# OR_timing_pulse.net
KiCad netlist of a schematic drawn in EAGLE
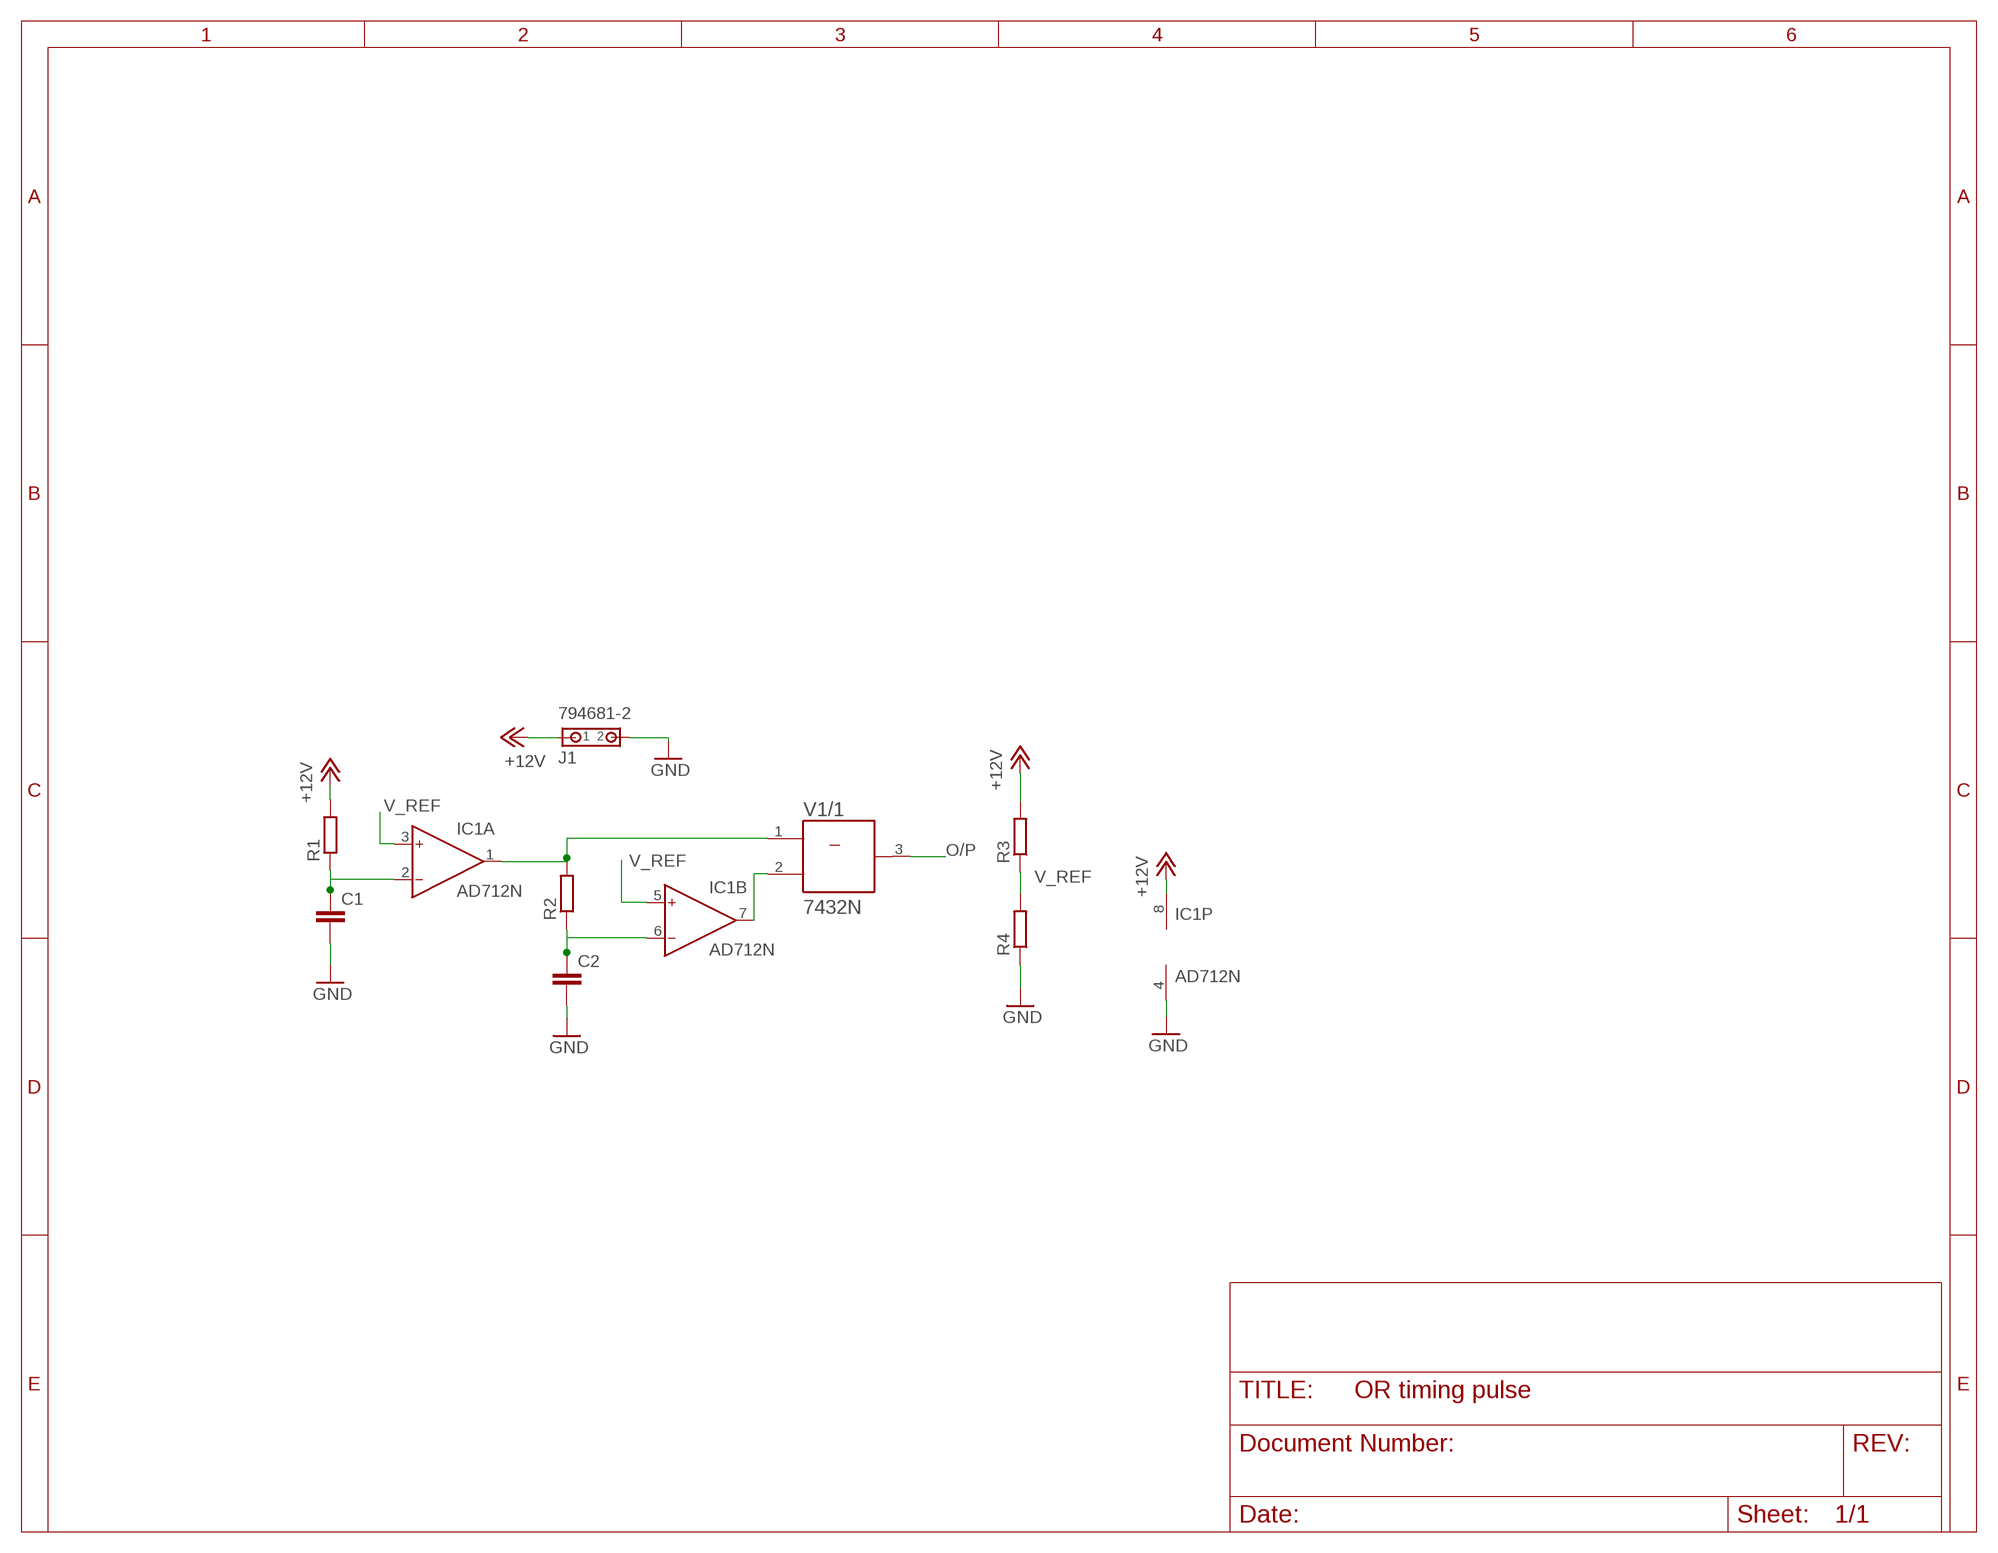
[diagram p0: schematic, sheet 1]

(export (version "E")
  (design (tool "Eeschema 10.0.6"))
  (components
    (comp (ref "C1")
      (value "C-EUC0805")
      (footprint "eagle-import:C0805")
      (libsource (lib "eagle-import") (part "C-EUC0805"))
    )
    (comp (ref "C2")
      (value "C-EUC0805")
      (footprint "eagle-import:C0805")
      (libsource (lib "eagle-import") (part "C-EUC0805"))
    )
    (comp (ref "IC1")
      (value "AD712N")
      (footprint "eagle-import:DIL08")
      (fields (field (name "MF") "ALTERA CORPORATION") (field (name "MPN") "AD712JNZ"))
      (libsource (lib "eagle-import") (part "AD712N"))
    )
    (comp (ref "J1")
      (value "794681-2")
      (footprint "eagle-import:794681-2")
      (libsource (lib "eagle-import") (part "794681-2"))
    )
    (comp (ref "R1")
      (value "R-EU_R0805")
      (footprint "eagle-import:R0805")
      (libsource (lib "eagle-import") (part "R-EU_R0805"))
    )
    (comp (ref "R2")
      (value "R-EU_R0805")
      (footprint "eagle-import:R0805")
      (libsource (lib "eagle-import") (part "R-EU_R0805"))
    )
    (comp (ref "R3")
      (value "R-EU_R0805")
      (footprint "eagle-import:R0805")
      (libsource (lib "eagle-import") (part "R-EU_R0805"))
    )
    (comp (ref "R4")
      (value "R-EU_R0805")
      (footprint "eagle-import:R0805")
      (libsource (lib "eagle-import") (part "R-EU_R0805"))
    )
    (comp (ref "V1")
      (value "7432N")
      (footprint "eagle-import:DIL14")
      (libsource (lib "eagle-import") (part "7432N"))
    )
  )
  (nets
    (net (code "1") (name "+12V") (class "Default")
      (node (ref "IC1") (pin "8") (pinfunction "V+_8") (pintype "power_in"))
      (node (ref "J1") (pin "1") (pinfunction "1_1") (pintype "passive"))
      (node (ref "R1") (pin "2") (pinfunction "2_2") (pintype "passive"))
      (node (ref "R3") (pin "2") (pinfunction "2_2") (pintype "passive"))
    )
    (net (code "2") (name "/O{slash}P") (class "Default")
      (node (ref "V1") (pin "3") (pinfunction "Y_3") (pintype "output"))
    )
    (net (code "3") (name "/V_REF") (class "Default")
      (node (ref "IC1") (pin "3") (pinfunction "IN+_3") (pintype "input"))
      (node (ref "IC1") (pin "5") (pinfunction "IN+_5") (pintype "input"))
      (node (ref "R3") (pin "1") (pinfunction "1_1") (pintype "passive"))
      (node (ref "R4") (pin "2") (pinfunction "2_2") (pintype "passive"))
    )
    (net (code "4") (name "GND") (class "Default")
      (node (ref "C1") (pin "2") (pinfunction "2_2") (pintype "passive"))
      (node (ref "C2") (pin "2") (pinfunction "2_2") (pintype "passive"))
      (node (ref "IC1") (pin "4") (pinfunction "V-_4") (pintype "power_in"))
      (node (ref "J1") (pin "2") (pinfunction "2_2") (pintype "passive"))
      (node (ref "R4") (pin "1") (pinfunction "1_1") (pintype "passive"))
    )
    (net (code "5") (name "Net-(IC1A-IN-)") (class "Default")
      (node (ref "C1") (pin "1") (pinfunction "1_1") (pintype "passive"))
      (node (ref "IC1") (pin "2") (pinfunction "IN-_2") (pintype "input"))
      (node (ref "R1") (pin "1") (pinfunction "1_1") (pintype "passive"))
    )
    (net (code "6") (name "Net-(IC1A-OUT)") (class "Default")
      (node (ref "IC1") (pin "1") (pinfunction "OUT_1") (pintype "output"))
      (node (ref "R2") (pin "2") (pinfunction "2_2") (pintype "passive"))
      (node (ref "V1") (pin "1") (pinfunction "A_1") (pintype "input"))
    )
    (net (code "7") (name "Net-(IC1B-IN-)") (class "Default")
      (node (ref "C2") (pin "1") (pinfunction "1_1") (pintype "passive"))
      (node (ref "IC1") (pin "6") (pinfunction "IN-_6") (pintype "input"))
      (node (ref "R2") (pin "1") (pinfunction "1_1") (pintype "passive"))
    )
    (net (code "8") (name "Net-(IC1B-OUT)") (class "Default")
      (node (ref "IC1") (pin "7") (pinfunction "OUT_7") (pintype "output"))
      (node (ref "V1") (pin "2") (pinfunction "B_2") (pintype "input"))
    )
  )
)
